# esp32_module.net
KiCad netlist of a schematic drawn in EAGLE
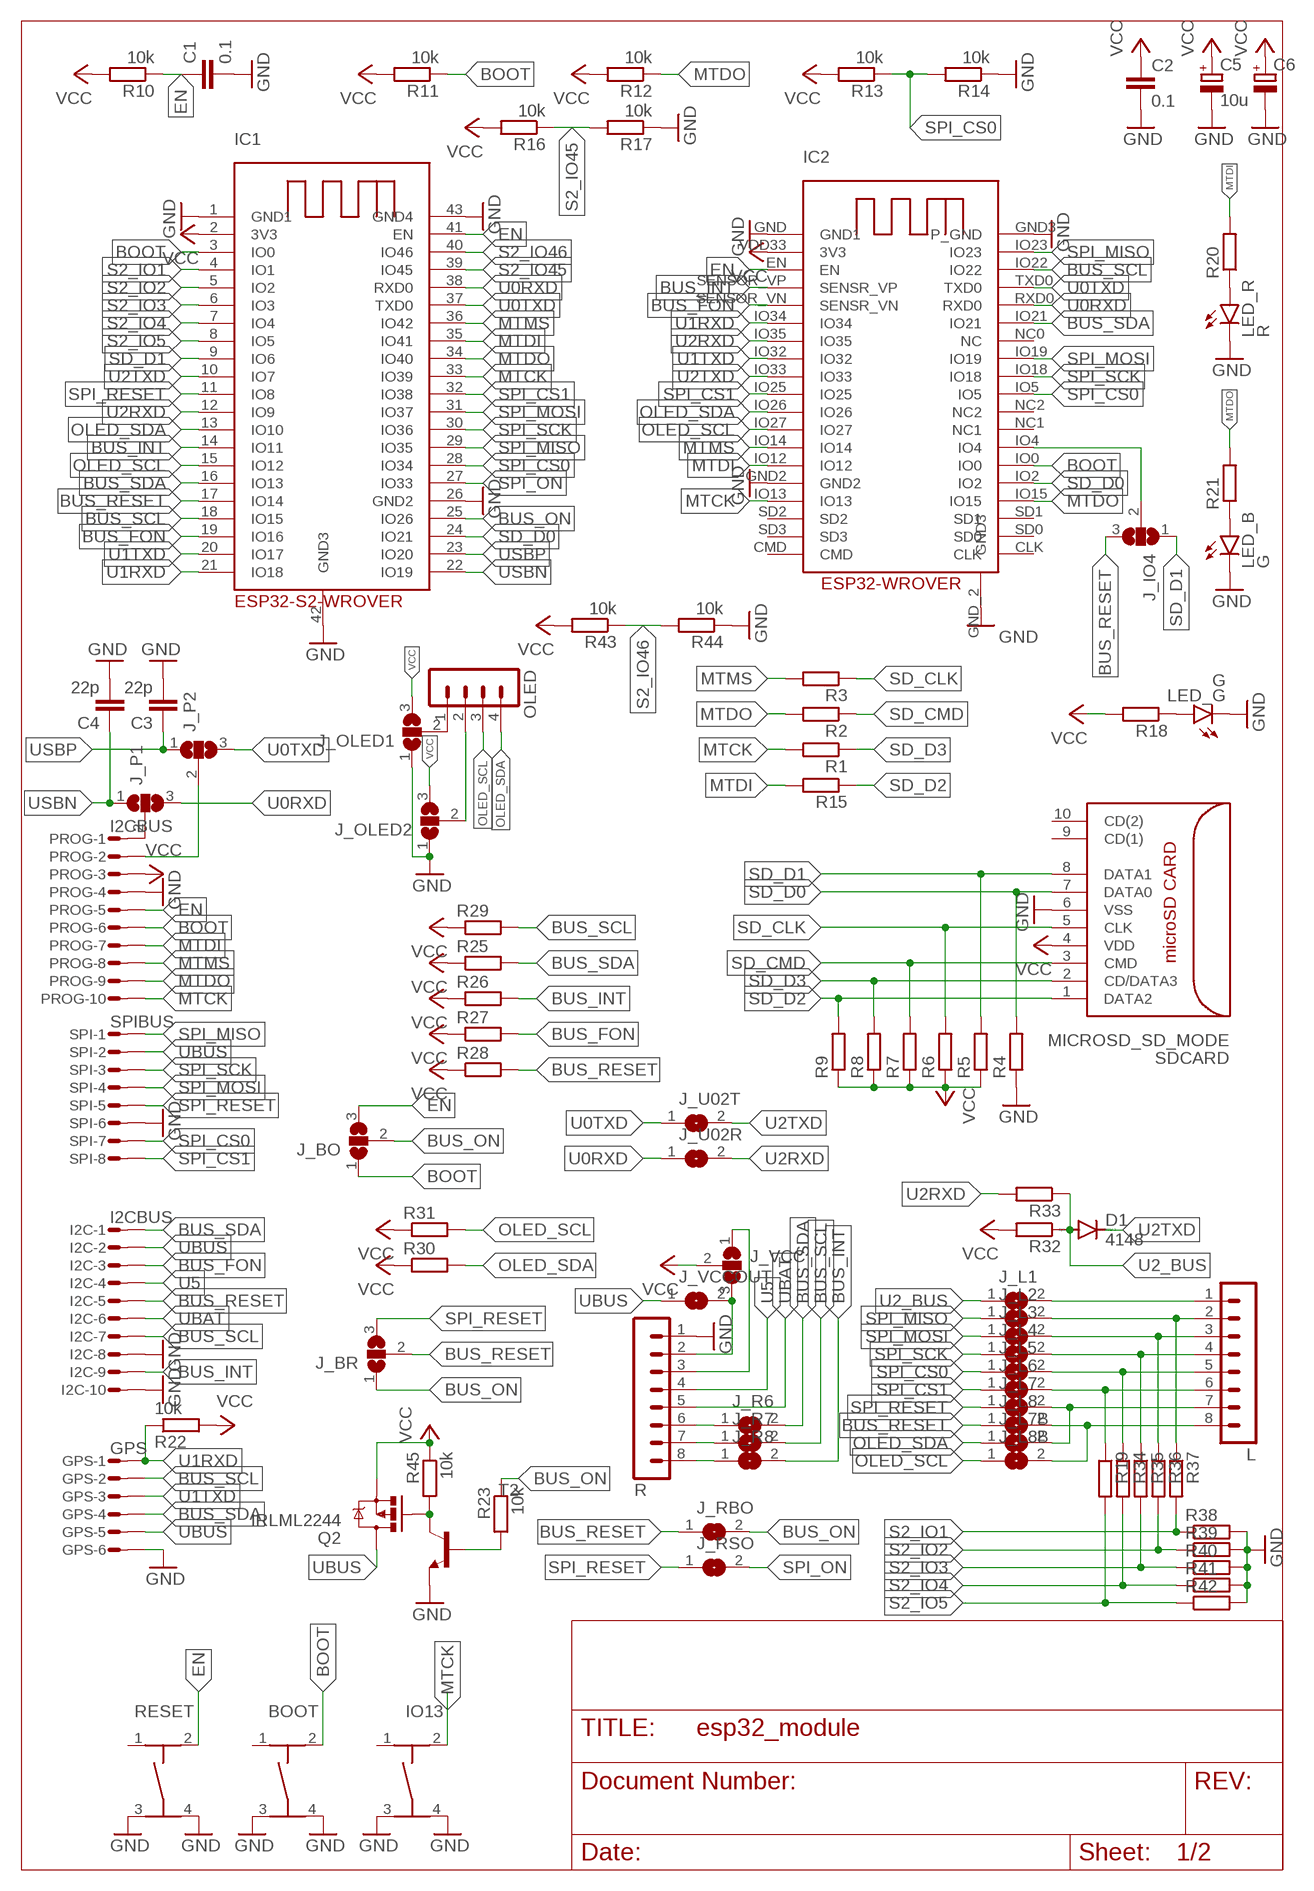
[diagram p0: schematic, sheet 1]

(export (version "E")
  (design (tool "Eeschema 10.0.6"))
  (components
    (comp (ref "BOOT")
      (value "TASTER-9314_SMD")
      (footprint "eagle-import:TASTER-9314_SMD")
      (libsource (lib "eagle-import") (part "TASTER-9314_SMD"))
    )
    (comp (ref "C1")
      (value "0.1")
      (footprint "eagle-import:C0805")
      (libsource (lib "eagle-import") (part "C-EUC0805"))
    )
    (comp (ref "C2")
      (value "0.1")
      (footprint "eagle-import:C0805")
      (libsource (lib "eagle-import") (part "C-EUC0805"))
    )
    (comp (ref "C3")
      (value "22p")
      (footprint "eagle-import:C0805")
      (libsource (lib "eagle-import") (part "C-EUC0805"))
    )
    (comp (ref "C4")
      (value "22p")
      (footprint "eagle-import:C0805")
      (libsource (lib "eagle-import") (part "C-EUC0805"))
    )
    (comp (ref "C5")
      (value "10u")
      (footprint "eagle-import:B_3528-21W")
      (libsource (lib "eagle-import") (part "CPOL-EUB/3528-21W"))
    )
    (comp (ref "C6")
      (value "CPOL-EUC/6032-28R")
      (footprint "eagle-import:C_6032-28R")
      (libsource (lib "eagle-import") (part "CPOL-EUC/6032-28R"))
    )
    (comp (ref "D1")
      (value "4148")
      (footprint "eagle-import:MINIMELF")
      (libsource (lib "eagle-import") (part "DIODE-MINIMELF"))
    )
    (comp (ref "GPS")
      (value "GPS")
      (footprint "eagle-import:MICROMATCH-6SMD")
      (libsource (lib "eagle-import") (part "MICROMATCH-6SMD"))
    )
    (comp (ref "I2C")
      (value "I2CBUS")
      (footprint "eagle-import:MICROMATCH-10SMD")
      (libsource (lib "eagle-import") (part "MICROMATCH-10SMD"))
    )
    (comp (ref "IC1")
      (value "ESP32-S2_WROVER")
      (footprint "eagle-import:ESP32-S2-WROVER")
      (libsource (lib "eagle-import") (part "ESP32-S2_WROVER"))
    )
    (comp (ref "IC2")
      (value "ESP32-WROVER")
      (footprint "eagle-import:ESP32-WROVER")
      (libsource (lib "eagle-import") (part "ESP32-WROVER"))
    )
    (comp (ref "IO13")
      (value "TASTER-9314_SMD")
      (footprint "eagle-import:TASTER-9314_SMD")
      (libsource (lib "eagle-import") (part "TASTER-9314_SMD"))
    )
    (comp (ref "J_BO")
      (value "SJ2W")
      (footprint "eagle-import:SJ_2")
      (libsource (lib "eagle-import") (part "SJ2W"))
    )
    (comp (ref "J_BR")
      (value "SJ2W")
      (footprint "eagle-import:SJ_2")
      (libsource (lib "eagle-import") (part "SJ2W"))
    )
    (comp (ref "J_IO4")
      (value "SJ2W")
      (footprint "eagle-import:SJ_2")
      (libsource (lib "eagle-import") (part "SJ2W"))
    )
    (comp (ref "J_L1")
      (value "SJ")
      (footprint "eagle-import:SJ")
      (libsource (lib "eagle-import") (part "SJ"))
    )
    (comp (ref "J_L2")
      (value "SJ")
      (footprint "eagle-import:SJ")
      (libsource (lib "eagle-import") (part "SJ"))
    )
    (comp (ref "J_L3")
      (value "SJ")
      (footprint "eagle-import:SJ")
      (libsource (lib "eagle-import") (part "SJ"))
    )
    (comp (ref "J_L4")
      (value "SJ")
      (footprint "eagle-import:SJ")
      (libsource (lib "eagle-import") (part "SJ"))
    )
    (comp (ref "J_L5")
      (value "SJ")
      (footprint "eagle-import:SJ")
      (libsource (lib "eagle-import") (part "SJ"))
    )
    (comp (ref "J_L6")
      (value "SJ")
      (footprint "eagle-import:SJ")
      (libsource (lib "eagle-import") (part "SJ"))
    )
    (comp (ref "J_L7")
      (value "SJ")
      (footprint "eagle-import:SJ")
      (libsource (lib "eagle-import") (part "SJ"))
    )
    (comp (ref "J_L7B")
      (value "SJ")
      (footprint "eagle-import:SJ")
      (libsource (lib "eagle-import") (part "SJ"))
    )
    (comp (ref "J_L8")
      (value "SJ")
      (footprint "eagle-import:SJ")
      (libsource (lib "eagle-import") (part "SJ"))
    )
    (comp (ref "J_L8B")
      (value "SJ")
      (footprint "eagle-import:SJ")
      (libsource (lib "eagle-import") (part "SJ"))
    )
    (comp (ref "J_OLED1")
      (value "SJ2W")
      (footprint "eagle-import:SJ_2")
      (libsource (lib "eagle-import") (part "SJ2W"))
    )
    (comp (ref "J_OLED2")
      (value "SJ2W")
      (footprint "eagle-import:SJ_2")
      (libsource (lib "eagle-import") (part "SJ2W"))
    )
    (comp (ref "J_P1")
      (value "SJ2W")
      (footprint "eagle-import:SJ_2")
      (libsource (lib "eagle-import") (part "SJ2W"))
    )
    (comp (ref "J_P2")
      (value "SJ2W")
      (footprint "eagle-import:SJ_2")
      (libsource (lib "eagle-import") (part "SJ2W"))
    )
    (comp (ref "J_R6")
      (value "SJ")
      (footprint "eagle-import:SJ")
      (libsource (lib "eagle-import") (part "SJ"))
    )
    (comp (ref "J_R7")
      (value "SJ")
      (footprint "eagle-import:SJ")
      (libsource (lib "eagle-import") (part "SJ"))
    )
    (comp (ref "J_R8")
      (value "SJ")
      (footprint "eagle-import:SJ")
      (libsource (lib "eagle-import") (part "SJ"))
    )
    (comp (ref "J_RBO")
      (value "SJ")
      (footprint "eagle-import:SJ")
      (libsource (lib "eagle-import") (part "SJ"))
    )
    (comp (ref "J_RSO")
      (value "SJ")
      (footprint "eagle-import:SJ")
      (libsource (lib "eagle-import") (part "SJ"))
    )
    (comp (ref "J_U02R")
      (value "SJ")
      (footprint "eagle-import:SJ")
      (libsource (lib "eagle-import") (part "SJ"))
    )
    (comp (ref "J_U02T")
      (value "SJ")
      (footprint "eagle-import:SJ")
      (libsource (lib "eagle-import") (part "SJ"))
    )
    (comp (ref "J_VCC")
      (value "SJ2W")
      (footprint "eagle-import:SJ_2")
      (libsource (lib "eagle-import") (part "SJ2W"))
    )
    (comp (ref "J_VCCOUT")
      (value "SJ")
      (footprint "eagle-import:SJ")
      (libsource (lib "eagle-import") (part "SJ"))
    )
    (comp (ref "L")
      (value "MA08-1")
      (footprint "eagle-import:MA08-1")
      (libsource (lib "eagle-import") (part "MA08-1"))
    )
    (comp (ref "LED_B")
      (value "G")
      (footprint "eagle-import:CHIPLED_0805")
      (libsource (lib "eagle-import") (part "LEDCHIPLED_0805"))
    )
    (comp (ref "LED_G")
      (value "G")
      (footprint "eagle-import:CHIPLED_0805")
      (libsource (lib "eagle-import") (part "LEDCHIPLED_0805"))
    )
    (comp (ref "LED_R")
      (value "R")
      (footprint "eagle-import:CHIPLED_0805")
      (libsource (lib "eagle-import") (part "LEDCHIPLED_0805"))
    )
    (comp (ref "OLED")
      (value "MA04-1")
      (footprint "eagle-import:MA04-1")
      (libsource (lib "eagle-import") (part "MA04-1"))
    )
    (comp (ref "PROG")
      (value "I2CBUS")
      (footprint "eagle-import:MICROMATCH-10SMD")
      (libsource (lib "eagle-import") (part "MICROMATCH-10SMD"))
    )
    (comp (ref "Q2")
      (value "IRLML2244")
      (footprint "eagle-import:SOT23-3")
      (libsource (lib "eagle-import") (part "MOSFET-PCHANNELIRLML2244"))
    )
    (comp (ref "R")
      (value "MA08-1")
      (footprint "eagle-import:MA08-1")
      (libsource (lib "eagle-import") (part "MA08-1"))
    )
    (comp (ref "R1")
      (value "R-EU_R0805")
      (footprint "eagle-import:R0805")
      (libsource (lib "eagle-import") (part "R-EU_R0805"))
    )
    (comp (ref "R2")
      (value "R-EU_R0805")
      (footprint "eagle-import:R0805")
      (libsource (lib "eagle-import") (part "R-EU_R0805"))
    )
    (comp (ref "R3")
      (value "R-EU_R0805")
      (footprint "eagle-import:R0805")
      (libsource (lib "eagle-import") (part "R-EU_R0805"))
    )
    (comp (ref "R4")
      (value "R-EU_R0805")
      (footprint "eagle-import:R0805")
      (libsource (lib "eagle-import") (part "R-EU_R0805"))
    )
    (comp (ref "R5")
      (value "R-EU_R0805")
      (footprint "eagle-import:R0805")
      (libsource (lib "eagle-import") (part "R-EU_R0805"))
    )
    (comp (ref "R6")
      (value "R-EU_R0805")
      (footprint "eagle-import:R0805")
      (libsource (lib "eagle-import") (part "R-EU_R0805"))
    )
    (comp (ref "R7")
      (value "R-EU_R0805")
      (footprint "eagle-import:R0805")
      (libsource (lib "eagle-import") (part "R-EU_R0805"))
    )
    (comp (ref "R8")
      (value "R-EU_R0805")
      (footprint "eagle-import:R0805")
      (libsource (lib "eagle-import") (part "R-EU_R0805"))
    )
    (comp (ref "R9")
      (value "R-EU_R0805")
      (footprint "eagle-import:R0805")
      (libsource (lib "eagle-import") (part "R-EU_R0805"))
    )
    (comp (ref "R10")
      (value "10k")
      (footprint "eagle-import:R0805")
      (libsource (lib "eagle-import") (part "R-EU_R0805"))
    )
    (comp (ref "R11")
      (value "10k")
      (footprint "eagle-import:R0805")
      (libsource (lib "eagle-import") (part "R-EU_R0805"))
    )
    (comp (ref "R12")
      (value "10k")
      (footprint "eagle-import:R0805")
      (libsource (lib "eagle-import") (part "R-EU_R0805"))
    )
    (comp (ref "R13")
      (value "10k")
      (footprint "eagle-import:R0805")
      (libsource (lib "eagle-import") (part "R-EU_R0805"))
    )
    (comp (ref "R14")
      (value "10k")
      (footprint "eagle-import:R0805")
      (libsource (lib "eagle-import") (part "R-EU_R0805"))
    )
    (comp (ref "R15")
      (value "R-EU_R0805")
      (footprint "eagle-import:R0805")
      (libsource (lib "eagle-import") (part "R-EU_R0805"))
    )
    (comp (ref "R16")
      (value "10k")
      (footprint "eagle-import:R0805")
      (libsource (lib "eagle-import") (part "R-EU_R0805"))
    )
    (comp (ref "R17")
      (value "10k")
      (footprint "eagle-import:R0805")
      (libsource (lib "eagle-import") (part "R-EU_R0805"))
    )
    (comp (ref "R18")
      (value "R-EU_R0603")
      (footprint "eagle-import:R0603")
      (libsource (lib "eagle-import") (part "R-EU_R0603"))
    )
    (comp (ref "R19")
      (value "R-EU_R0805")
      (footprint "eagle-import:R0805")
      (libsource (lib "eagle-import") (part "R-EU_R0805"))
    )
    (comp (ref "R20")
      (value "R-EU_R0603")
      (footprint "eagle-import:R0603")
      (libsource (lib "eagle-import") (part "R-EU_R0603"))
    )
    (comp (ref "R21")
      (value "R-EU_R0603")
      (footprint "eagle-import:R0603")
      (libsource (lib "eagle-import") (part "R-EU_R0603"))
    )
    (comp (ref "R22")
      (value "10k")
      (footprint "eagle-import:R0805")
      (libsource (lib "eagle-import") (part "R-EU_R0805"))
    )
    (comp (ref "R23")
      (value "10k")
      (footprint "eagle-import:R0805")
      (libsource (lib "eagle-import") (part "R-EU_R0805"))
    )
    (comp (ref "R25")
      (value "R-EU_R0805")
      (footprint "eagle-import:R0805")
      (libsource (lib "eagle-import") (part "R-EU_R0805"))
    )
    (comp (ref "R26")
      (value "R-EU_R0805")
      (footprint "eagle-import:R0805")
      (libsource (lib "eagle-import") (part "R-EU_R0805"))
    )
    (comp (ref "R27")
      (value "R-EU_R0805")
      (footprint "eagle-import:R0805")
      (libsource (lib "eagle-import") (part "R-EU_R0805"))
    )
    (comp (ref "R28")
      (value "R-EU_R0805")
      (footprint "eagle-import:R0805")
      (libsource (lib "eagle-import") (part "R-EU_R0805"))
    )
    (comp (ref "R29")
      (value "R-EU_R0805")
      (footprint "eagle-import:R0805")
      (libsource (lib "eagle-import") (part "R-EU_R0805"))
    )
    (comp (ref "R30")
      (value "R-EU_R0805")
      (footprint "eagle-import:R0805")
      (libsource (lib "eagle-import") (part "R-EU_R0805"))
    )
    (comp (ref "R31")
      (value "R-EU_R0805")
      (footprint "eagle-import:R0805")
      (libsource (lib "eagle-import") (part "R-EU_R0805"))
    )
    (comp (ref "R32")
      (value "R-EU_R0805")
      (footprint "eagle-import:R0805")
      (libsource (lib "eagle-import") (part "R-EU_R0805"))
    )
    (comp (ref "R33")
      (value "R-EU_R0805")
      (footprint "eagle-import:R0805")
      (libsource (lib "eagle-import") (part "R-EU_R0805"))
    )
    (comp (ref "R34")
      (value "R-EU_R0805")
      (footprint "eagle-import:R0805")
      (libsource (lib "eagle-import") (part "R-EU_R0805"))
    )
    (comp (ref "R35")
      (value "R-EU_R0805")
      (footprint "eagle-import:R0805")
      (libsource (lib "eagle-import") (part "R-EU_R0805"))
    )
    (comp (ref "R36")
      (value "R-EU_R0805")
      (footprint "eagle-import:R0805")
      (libsource (lib "eagle-import") (part "R-EU_R0805"))
    )
    (comp (ref "R37")
      (value "R-EU_R0805")
      (footprint "eagle-import:R0805")
      (libsource (lib "eagle-import") (part "R-EU_R0805"))
    )
    (comp (ref "R38")
      (value "R-EU_R0805")
      (footprint "eagle-import:R0805")
      (libsource (lib "eagle-import") (part "R-EU_R0805"))
    )
    (comp (ref "R39")
      (value "R-EU_R0805")
      (footprint "eagle-import:R0805")
      (libsource (lib "eagle-import") (part "R-EU_R0805"))
    )
    (comp (ref "R40")
      (value "R-EU_R0805")
      (footprint "eagle-import:R0805")
      (libsource (lib "eagle-import") (part "R-EU_R0805"))
    )
    (comp (ref "R41")
      (value "R-EU_R0805")
      (footprint "eagle-import:R0805")
      (libsource (lib "eagle-import") (part "R-EU_R0805"))
    )
    (comp (ref "R42")
      (value "R-EU_R0805")
      (footprint "eagle-import:R0805")
      (libsource (lib "eagle-import") (part "R-EU_R0805"))
    )
    (comp (ref "R43")
      (value "10k")
      (footprint "eagle-import:R0805")
      (libsource (lib "eagle-import") (part "R-EU_R0805"))
    )
    (comp (ref "R44")
      (value "10k")
      (footprint "eagle-import:R0805")
      (libsource (lib "eagle-import") (part "R-EU_R0805"))
    )
    (comp (ref "R45")
      (value "10k")
      (footprint "eagle-import:R0805")
      (libsource (lib "eagle-import") (part "R-EU_R0805"))
    )
    (comp (ref "RESET")
      (value "TASTER-9314_SMD")
      (footprint "eagle-import:TASTER-9314_SMD")
      (libsource (lib "eagle-import") (part "TASTER-9314_SMD"))
    )
    (comp (ref "SDCARD")
      (value "MICROSD_SD_MODE")
      (footprint "eagle-import:MICRO_SD_CONNECTOR")
      (libsource (lib "eagle-import") (part "MICROSD_SD_MODE"))
    )
    (comp (ref "SPI")
      (value "SPIBUS")
      (footprint "eagle-import:MICROMATCH-8-SMD")
      (libsource (lib "eagle-import") (part "MICROMATCH-8SMD"))
    )
    (comp (ref "T2")
      (value "BC817-16-NPN-SOT23-BEC")
      (footprint "eagle-import:SOT23-BEC")
      (libsource (lib "eagle-import") (part "-NPN-SOT23-BECBC817-16"))
    )
  )
  (nets
    (net (code "1") (name "BOOT") (class "Default")
      (node (ref "BOOT") (pin "2") (pinfunction "2_2") (pintype "passive"))
      (node (ref "IC1") (pin "3") (pinfunction "IO0_3") (pintype "bidirectional"))
      (node (ref "IC2") (pin "IO0") (pinfunction "IO0_IO0") (pintype "bidirectional"))
      (node (ref "J_BO") (pin "1") (pinfunction "1_1") (pintype "passive"))
      (node (ref "PROG") (pin "6") (pinfunction "S_6") (pintype "passive"))
      (node (ref "R11") (pin "1") (pinfunction "1_1") (pintype "passive"))
    )
    (net (code "2") (name "BUS_FON") (class "Default")
      (node (ref "I2C") (pin "3") (pinfunction "S_3") (pintype "passive"))
      (node (ref "IC1") (pin "19") (pinfunction "IO16_19") (pintype "bidirectional"))
      (node (ref "IC2") (pin "SENSOR_VN") (pinfunction "SENSR_VN_SENSOR_VN") (pintype "bidirectional"))
      (node (ref "R27") (pin "2") (pinfunction "2_2") (pintype "passive"))
    )
    (net (code "3") (name "BUS_INT") (class "Default")
      (node (ref "I2C") (pin "9") (pinfunction "S_9") (pintype "passive"))
      (node (ref "IC1") (pin "14") (pinfunction "IO11_14") (pintype "bidirectional"))
      (node (ref "IC2") (pin "SENSOR_VP") (pinfunction "SENSR_VP_SENSOR_VP") (pintype "bidirectional"))
      (node (ref "J_R8") (pin "2") (pinfunction "2_2") (pintype "passive"))
      (node (ref "R26") (pin "2") (pinfunction "2_2") (pintype "passive"))
    )
    (net (code "4") (name "BUS_ON") (class "Default")
      (node (ref "IC1") (pin "25") (pinfunction "IO26_25") (pintype "bidirectional"))
      (node (ref "J_BO") (pin "2") (pinfunction "2_2") (pintype "passive"))
      (node (ref "J_BR") (pin "1") (pinfunction "1_1") (pintype "passive"))
      (node (ref "J_RBO") (pin "2") (pinfunction "2_2") (pintype "passive"))
      (node (ref "R23") (pin "1") (pinfunction "1_1") (pintype "passive"))
    )
    (net (code "5") (name "BUS_RESET") (class "Default")
      (node (ref "I2C") (pin "5") (pinfunction "S_5") (pintype "passive"))
      (node (ref "IC1") (pin "17") (pinfunction "IO14_17") (pintype "bidirectional"))
      (node (ref "J_BR") (pin "2") (pinfunction "2_2") (pintype "passive"))
      (node (ref "J_IO4") (pin "3") (pinfunction "3_3") (pintype "passive"))
      (node (ref "J_L8") (pin "1") (pinfunction "1_1") (pintype "passive"))
      (node (ref "J_RBO") (pin "1") (pinfunction "1_1") (pintype "passive"))
      (node (ref "R28") (pin "2") (pinfunction "2_2") (pintype "passive"))
    )
    (net (code "6") (name "BUS_SCL") (class "Default")
      (node (ref "GPS") (pin "2") (pinfunction "S_2") (pintype "passive"))
      (node (ref "I2C") (pin "7") (pinfunction "S_7") (pintype "passive"))
      (node (ref "IC1") (pin "18") (pinfunction "IO15_18") (pintype "bidirectional"))
      (node (ref "IC2") (pin "IO22") (pinfunction "IO22_IO22") (pintype "bidirectional"))
      (node (ref "J_R7") (pin "2") (pinfunction "2_2") (pintype "passive"))
      (node (ref "R29") (pin "2") (pinfunction "2_2") (pintype "passive"))
    )
    (net (code "7") (name "BUS_SDA") (class "Default")
      (node (ref "GPS") (pin "4") (pinfunction "S_4") (pintype "passive"))
      (node (ref "I2C") (pin "1") (pinfunction "S_1") (pintype "passive"))
      (node (ref "IC1") (pin "16") (pinfunction "IO13_16") (pintype "bidirectional"))
      (node (ref "IC2") (pin "IO21") (pinfunction "IO21_IO21") (pintype "bidirectional"))
      (node (ref "J_R6") (pin "2") (pinfunction "2_2") (pintype "passive"))
      (node (ref "R25") (pin "2") (pinfunction "2_2") (pintype "passive"))
    )
    (net (code "8") (name "EN") (class "Default")
      (node (ref "C1") (pin "1") (pinfunction "1_1") (pintype "passive"))
      (node (ref "IC1") (pin "41") (pinfunction "EN_41") (pintype "input"))
      (node (ref "IC2") (pin "EN") (pinfunction "EN_EN") (pintype "bidirectional"))
      (node (ref "J_BO") (pin "3") (pinfunction "3_3") (pintype "passive"))
      (node (ref "PROG") (pin "5") (pinfunction "S_5") (pintype "passive"))
      (node (ref "R10") (pin "1") (pinfunction "1_1") (pintype "passive"))
      (node (ref "RESET") (pin "2") (pinfunction "2_2") (pintype "passive"))
    )
    (net (code "9") (name "GND") (class "Default")
      (node (ref "BOOT") (pin "3") (pinfunction "3_3") (pintype "passive"))
      (node (ref "BOOT") (pin "4") (pinfunction "4_4") (pintype "passive"))
      (node (ref "C1") (pin "2") (pinfunction "2_2") (pintype "passive"))
      (node (ref "C2") (pin "2") (pinfunction "2_2") (pintype "passive"))
      (node (ref "C3") (pin "2") (pinfunction "2_2") (pintype "passive"))
      (node (ref "C4") (pin "2") (pinfunction "2_2") (pintype "passive"))
      (node (ref "C5") (pin "-") (pinfunction "-_-") (pintype "passive"))
      (node (ref "C6") (pin "-") (pinfunction "-_-") (pintype "passive"))
      (node (ref "GPS") (pin "6") (pinfunction "S_6") (pintype "passive"))
      (node (ref "I2C") (pin "10") (pinfunction "S_10") (pintype "passive"))
      (node (ref "I2C") (pin "8") (pinfunction "S_8") (pintype "passive"))
      (node (ref "IC1") (pin "1") (pinfunction "GND1_1") (pintype "passive"))
      (node (ref "IC1") (pin "26") (pinfunction "GND2_26") (pintype "passive"))
      (node (ref "IC1") (pin "42") (pinfunction "GND3_42") (pintype "passive"))
      (node (ref "IC1") (pin "43") (pinfunction "GND4_43") (pintype "passive"))
      (node (ref "IC2") (pin "GND") (pinfunction "GND1_GND") (pintype "bidirectional"))
      (node (ref "IC2") (pin "GND2") (pinfunction "GND2_GND2") (pintype "bidirectional"))
      (node (ref "IC2") (pin "GND3") (pinfunction "P_GND_GND3") (pintype "bidirectional"))
      (node (ref "IC2") (pin "GND_2") (pinfunction "GND3_GND_2") (pintype "bidirectional"))
      (node (ref "IO13") (pin "3") (pinfunction "3_3") (pintype "passive"))
      (node (ref "IO13") (pin "4") (pinfunction "4_4") (pintype "passive"))
      (node (ref "J_OLED1") (pin "1") (pinfunction "1_1") (pintype "passive"))
      (node (ref "J_OLED2") (pin "1") (pinfunction "1_1") (pintype "passive"))
      (node (ref "LED_B") (pin "C") (pinfunction "C_C") (pintype "passive"))
      (node (ref "LED_G") (pin "C") (pinfunction "C_C") (pintype "passive"))
      (node (ref "LED_R") (pin "C") (pinfunction "C_C") (pintype "passive"))
      (node (ref "PROG") (pin "4") (pinfunction "S_4") (pintype "passive"))
      (node (ref "R") (pin "1") (pinfunction "1_1") (pintype "passive"))
      (node (ref "R14") (pin "1") (pinfunction "1_1") (pintype "passive"))
      (node (ref "R17") (pin "1") (pinfunction "1_1") (pintype "passive"))
      (node (ref "R38") (pin "2") (pinfunction "2_2") (pintype "passive"))
      (node (ref "R39") (pin "2") (pinfunction "2_2") (pintype "passive"))
      (node (ref "R4") (pin "1") (pinfunction "1_1") (pintype "passive"))
      (node (ref "R40") (pin "2") (pinfunction "2_2") (pintype "passive"))
      (node (ref "R41") (pin "2") (pinfunction "2_2") (pintype "passive"))
      (node (ref "R42") (pin "2") (pinfunction "2_2") (pintype "passive"))
      (node (ref "R44") (pin "1") (pinfunction "1_1") (pintype "passive"))
      (node (ref "RESET") (pin "3") (pinfunction "3_3") (pintype "passive"))
      (node (ref "RESET") (pin "4") (pinfunction "4_4") (pintype "passive"))
      (node (ref "SDCARD") (pin "6") (pinfunction "VSS_6") (pintype "bidirectional"))
      (node (ref "SPI") (pin "6") (pinfunction "S_6") (pintype "passive"))
      (node (ref "T2") (pin "E") (pinfunction "E_E") (pintype "passive"))
    )
    (net (code "10") (name "MTCK") (class "Default")
      (node (ref "IC1") (pin "33") (pinfunction "IO39_33") (pintype "bidirectional"))
      (node (ref "IC2") (pin "IO13") (pinfunction "IO13_IO13") (pintype "bidirectional"))
      (node (ref "IO13") (pin "2") (pinfunction "2_2") (pintype "passive"))
      (node (ref "PROG") (pin "10") (pinfunction "S_10") (pintype "passive"))
      (node (ref "R1") (pin "2") (pinfunction "2_2") (pintype "passive"))
    )
    (net (code "11") (name "MTDI") (class "Default")
      (node (ref "IC1") (pin "35") (pinfunction "IO41_35") (pintype "bidirectional"))
      (node (ref "IC2") (pin "IO12") (pinfunction "IO12_IO12") (pintype "bidirectional"))
      (node (ref "PROG") (pin "7") (pinfunction "S_7") (pintype "passive"))
      (node (ref "R15") (pin "2") (pinfunction "2_2") (pintype "passive"))
      (node (ref "R20") (pin "2") (pinfunction "2_2") (pintype "passive"))
    )
    (net (code "12") (name "MTDO") (class "Default")
      (node (ref "IC1") (pin "34") (pinfunction "IO40_34") (pintype "bidirectional"))
      (node (ref "IC2") (pin "IO15") (pinfunction "IO15_IO15") (pintype "bidirectional"))
      (node (ref "PROG") (pin "9") (pinfunction "S_9") (pintype "passive"))
      (node (ref "R12") (pin "1") (pinfunction "1_1") (pintype "passive"))
      (node (ref "R2") (pin "2") (pinfunction "2_2") (pintype "passive"))
      (node (ref "R21") (pin "2") (pinfunction "2_2") (pintype "passive"))
    )
    (net (code "13") (name "MTMS") (class "Default")
      (node (ref "IC1") (pin "36") (pinfunction "IO42_36") (pintype "bidirectional"))
      (node (ref "IC2") (pin "IO14") (pinfunction "IO14_IO14") (pintype "bidirectional"))
      (node (ref "PROG") (pin "8") (pinfunction "S_8") (pintype "passive"))
      (node (ref "R3") (pin "2") (pinfunction "2_2") (pintype "passive"))
    )
    (net (code "14") (name "Net-(IC2-PadIO4)") (class "Default")
      (node (ref "IC2") (pin "IO4") (pinfunction "IO4_IO4") (pintype "bidirectional"))
      (node (ref "J_IO4") (pin "2") (pinfunction "2_2") (pintype "passive"))
    )
    (net (code "15") (name "Net-(J_L1-Pad2)") (class "Default")
      (node (ref "J_L1") (pin "2") (pinfunction "2_2") (pintype "passive"))
      (node (ref "L") (pin "1") (pinfunction "1_1") (pintype "passive"))
    )
    (net (code "16") (name "Net-(J_L2-Pad2)") (class "Default")
      (node (ref "J_L2") (pin "2") (pinfunction "2_2") (pintype "passive"))
      (node (ref "L") (pin "2") (pinfunction "2_2") (pintype "passive"))
      (node (ref "R37") (pin "1") (pinfunction "1_1") (pintype "passive"))
    )
    (net (code "17") (name "Net-(J_L3-Pad2)") (class "Default")
      (node (ref "J_L3") (pin "2") (pinfunction "2_2") (pintype "passive"))
      (node (ref "L") (pin "3") (pinfunction "3_3") (pintype "passive"))
      (node (ref "R36") (pin "1") (pinfunction "1_1") (pintype "passive"))
    )
    (net (code "18") (name "Net-(J_L4-Pad2)") (class "Default")
      (node (ref "J_L4") (pin "2") (pinfunction "2_2") (pintype "passive"))
      (node (ref "L") (pin "4") (pinfunction "4_4") (pintype "passive"))
      (node (ref "R35") (pin "1") (pinfunction "1_1") (pintype "passive"))
    )
    (net (code "19") (name "Net-(J_L5-Pad2)") (class "Default")
      (node (ref "J_L5") (pin "2") (pinfunction "2_2") (pintype "passive"))
      (node (ref "L") (pin "5") (pinfunction "5_5") (pintype "passive"))
      (node (ref "R34") (pin "1") (pinfunction "1_1") (pintype "passive"))
    )
    (net (code "20") (name "Net-(J_L6-Pad2)") (class "Default")
      (node (ref "J_L6") (pin "2") (pinfunction "2_2") (pintype "passive"))
      (node (ref "L") (pin "6") (pinfunction "6_6") (pintype "passive"))
      (node (ref "R19") (pin "1") (pinfunction "1_1") (pintype "passive"))
    )
    (net (code "21") (name "Net-(J_L7-Pad2)") (class "Default")
      (node (ref "J_L7") (pin "2") (pinfunction "2_2") (pintype "passive"))
      (node (ref "J_L7B") (pin "2") (pinfunction "2_2") (pintype "passive"))
      (node (ref "L") (pin "7") (pinfunction "7_7") (pintype "passive"))
    )
    (net (code "22") (name "Net-(J_L8-Pad2)") (class "Default")
      (node (ref "J_L8") (pin "2") (pinfunction "2_2") (pintype "passive"))
      (node (ref "J_L8B") (pin "2") (pinfunction "2_2") (pintype "passive"))
      (node (ref "L") (pin "8") (pinfunction "8_8") (pintype "passive"))
    )
    (net (code "23") (name "Net-(J_OLED1-Pad2)") (class "Default")
      (node (ref "J_OLED1") (pin "2") (pinfunction "2_2") (pintype "passive"))
      (node (ref "OLED") (pin "1") (pinfunction "1_1") (pintype "passive"))
    )
    (net (code "24") (name "Net-(J_OLED2-Pad2)") (class "Default")
      (node (ref "J_OLED2") (pin "2") (pinfunction "2_2") (pintype "passive"))
      (node (ref "OLED") (pin "2") (pinfunction "2_2") (pintype "passive"))
    )
    (net (code "25") (name "Net-(J_R6-Pad1)") (class "Default")
      (node (ref "J_R6") (pin "1") (pinfunction "1_1") (pintype "passive"))
      (node (ref "R") (pin "6") (pinfunction "6_6") (pintype "passive"))
    )
    (net (code "26") (name "Net-(J_R7-Pad1)") (class "Default")
      (node (ref "J_R7") (pin "1") (pinfunction "1_1") (pintype "passive"))
      (node (ref "R") (pin "7") (pinfunction "7_7") (pintype "passive"))
    )
    (net (code "27") (name "Net-(J_R8-Pad1)") (class "Default")
      (node (ref "J_R8") (pin "1") (pinfunction "1_1") (pintype "passive"))
      (node (ref "R") (pin "8") (pinfunction "8_8") (pintype "passive"))
    )
    (net (code "28") (name "Net-(J_VCC-Pad1)") (class "Default")
      (node (ref "J_VCC") (pin "1") (pinfunction "1_1") (pintype "passive"))
      (node (ref "R") (pin "3") (pinfunction "3_3") (pintype "passive"))
    )
    (net (code "29") (name "Net-(J_VCC-Pad3)") (class "Default")
      (node (ref "J_VCC") (pin "3") (pinfunction "3_3") (pintype "passive"))
      (node (ref "J_VCCOUT") (pin "2") (pinfunction "2_2") (pintype "passive"))
      (node (ref "R") (pin "2") (pinfunction "2_2") (pintype "passive"))
    )
    (net (code "30") (name "Net-(LED_B-PadA)") (class "Default")
      (node (ref "LED_B") (pin "A") (pinfunction "A_A") (pintype "passive"))
      (node (ref "R21") (pin "1") (pinfunction "1_1") (pintype "passive"))
    )
    (net (code "31") (name "Net-(LED_G-PadA)") (class "Default")
      (node (ref "LED_G") (pin "A") (pinfunction "A_A") (pintype "passive"))
      (node (ref "R18") (pin "1") (pinfunction "1_1") (pintype "passive"))
    )
    (net (code "32") (name "Net-(LED_R-PadA)") (class "Default")
      (node (ref "LED_R") (pin "A") (pinfunction "A_A") (pintype "passive"))
      (node (ref "R20") (pin "1") (pinfunction "1_1") (pintype "passive"))
    )
    (net (code "33") (name "Net-(PROGA-S)") (class "Default")
      (node (ref "J_P1") (pin "2") (pinfunction "2_2") (pintype "passive"))
      (node (ref "PROG") (pin "1") (pinfunction "S_1") (pintype "passive"))
    )
    (net (code "34") (name "Net-(PROGC-S)") (class "Default")
      (node (ref "J_P2") (pin "2") (pinfunction "2_2") (pintype "passive"))
      (node (ref "PROG") (pin "2") (pinfunction "S_2") (pintype "passive"))
    )
    (net (code "35") (name "Net-(Q2-G)") (class "Default")
      (node (ref "Q2") (pin "1") (pinfunction "G_1") (pintype "passive"))
      (node (ref "R45") (pin "2") (pinfunction "2_2") (pintype "passive"))
      (node (ref "T2") (pin "C") (pinfunction "C_C") (pintype "passive"))
    )
    (net (code "36") (name "Net-(R23-Pad2)") (class "Default")
      (node (ref "R23") (pin "2") (pinfunction "2_2") (pintype "passive"))
      (node (ref "T2") (pin "B") (pinfunction "B_B") (pintype "passive"))
    )
    (net (code "37") (name "OLED_SCL") (class "Default")
      (node (ref "IC1") (pin "15") (pinfunction "IO12_15") (pintype "bidirectional"))
      (node (ref "IC2") (pin "IO27") (pinfunction "IO27_IO27") (pintype "bidirectional"))
      (node (ref "J_L8B") (pin "1") (pinfunction "1_1") (pintype "passive"))
      (node (ref "OLED") (pin "3") (pinfunction "3_3") (pintype "passive"))
      (node (ref "R31") (pin "2") (pinfunction "2_2") (pintype "passive"))
    )
    (net (code "38") (name "OLED_SDA") (class "Default")
      (node (ref "IC1") (pin "13") (pinfunction "IO10_13") (pintype "bidirectional"))
      (node (ref "IC2") (pin "IO26") (pinfunction "IO26_IO26") (pintype "bidirectional"))
      (node (ref "J_L7B") (pin "1") (pinfunction "1_1") (pintype "passive"))
      (node (ref "OLED") (pin "4") (pinfunction "4_4") (pintype "passive"))
      (node (ref "R30") (pin "2") (pinfunction "2_2") (pintype "passive"))
    )
    (net (code "39") (name "S2_IO1") (class "Default")
      (node (ref "IC1") (pin "4") (pinfunction "IO1_4") (pintype "bidirectional"))
      (node (ref "R37") (pin "2") (pinfunction "2_2") (pintype "passive"))
      (node (ref "R38") (pin "1") (pinfunction "1_1") (pintype "passive"))
    )
    (net (code "40") (name "S2_IO2") (class "Default")
      (node (ref "IC1") (pin "5") (pinfunction "IO2_5") (pintype "bidirectional"))
      (node (ref "R36") (pin "2") (pinfunction "2_2") (pintype "passive"))
      (node (ref "R39") (pin "1") (pinfunction "1_1") (pintype "passive"))
    )
    (net (code "41") (name "S2_IO3") (class "Default")
      (node (ref "IC1") (pin "6") (pinfunction "IO3_6") (pintype "bidirectional"))
      (node (ref "R35") (pin "2") (pinfunction "2_2") (pintype "passive"))
      (node (ref "R40") (pin "1") (pinfunction "1_1") (pintype "passive"))
    )
    (net (code "42") (name "S2_IO4") (class "Default")
      (node (ref "IC1") (pin "7") (pinfunction "IO4_7") (pintype "bidirectional"))
      (node (ref "R34") (pin "2") (pinfunction "2_2") (pintype "passive"))
      (node (ref "R41") (pin "1") (pinfunction "1_1") (pintype "passive"))
    )
    (net (code "43") (name "S2_IO5") (class "Default")
      (node (ref "IC1") (pin "8") (pinfunction "IO5_8") (pintype "bidirectional"))
      (node (ref "R19") (pin "2") (pinfunction "2_2") (pintype "passive"))
      (node (ref "R42") (pin "1") (pinfunction "1_1") (pintype "passive"))
    )
    (net (code "44") (name "S2_IO45") (class "Default")
      (node (ref "IC1") (pin "39") (pinfunction "IO45_39") (pintype "bidirectional"))
      (node (ref "R16") (pin "1") (pinfunction "1_1") (pintype "passive"))
      (node (ref "R17") (pin "2") (pinfunction "2_2") (pintype "passive"))
    )
    (net (code "45") (name "S2_IO46") (class "Default")
      (node (ref "IC1") (pin "40") (pinfunction "IO46_40") (pintype "bidirectional"))
      (node (ref "R43") (pin "1") (pinfunction "1_1") (pintype "passive"))
      (node (ref "R44") (pin "2") (pinfunction "2_2") (pintype "passive"))
    )
    (net (code "46") (name "SD_CLK") (class "Default")
      (node (ref "R3") (pin "1") (pinfunction "1_1") (pintype "passive"))
      (node (ref "R6") (pin "2") (pinfunction "2_2") (pintype "passive"))
      (node (ref "SDCARD") (pin "5") (pinfunction "CLK_5") (pintype "bidirectional"))
    )
    (net (code "47") (name "SD_CMD") (class "Default")
      (node (ref "R2") (pin "1") (pinfunction "1_1") (pintype "passive"))
      (node (ref "R7") (pin "2") (pinfunction "2_2") (pintype "passive"))
      (node (ref "SDCARD") (pin "3") (pinfunction "CMD_3") (pintype "bidirectional"))
    )
    (net (code "48") (name "SD_D0") (class "Default")
      (node (ref "IC1") (pin "24") (pinfunction "IO21_24") (pintype "bidirectional"))
      (node (ref "IC2") (pin "IO2") (pinfunction "IO2_IO2") (pintype "bidirectional"))
      (node (ref "R4") (pin "2") (pinfunction "2_2") (pintype "passive"))
      (node (ref "SDCARD") (pin "7") (pinfunction "DATA0_7") (pintype "bidirectional"))
    )
    (net (code "49") (name "SD_D1") (class "Default")
      (node (ref "IC1") (pin "9") (pinfunction "IO6_9") (pintype "bidirectional"))
      (node (ref "J_IO4") (pin "1") (pinfunction "1_1") (pintype "passive"))
      (node (ref "R5") (pin "2") (pinfunction "2_2") (pintype "passive"))
      (node (ref "SDCARD") (pin "8") (pinfunction "DATA1_8") (pintype "bidirectional"))
    )
    (net (code "50") (name "SD_D2") (class "Default")
      (node (ref "R15") (pin "1") (pinfunction "1_1") (pintype "passive"))
      (node (ref "R9") (pin "2") (pinfunction "2_2") (pintype "passive"))
      (node (ref "SDCARD") (pin "1") (pinfunction "DATA2_1") (pintype "bidirectional"))
    )
    (net (code "51") (name "SD_D3") (class "Default")
      (node (ref "R1") (pin "1") (pinfunction "1_1") (pintype "passive"))
      (node (ref "R8") (pin "2") (pinfunction "2_2") (pintype "passive"))
      (node (ref "SDCARD") (pin "2") (pinfunction "CD/DATA3_2") (pintype "bidirectional"))
    )
    (net (code "52") (name "SPI_CS0") (class "Default")
      (node (ref "IC1") (pin "28") (pinfunction "IO34_28") (pintype "bidirectional"))
      (node (ref "IC2") (pin "IO5") (pinfunction "IO5_IO5") (pintype "bidirectional"))
      (node (ref "J_L5") (pin "1") (pinfunction "1_1") (pintype "passive"))
      (node (ref "R13") (pin "1") (pinfunction "1_1") (pintype "passive"))
      (node (ref "R14") (pin "2") (pinfunction "2_2") (pintype "passive"))
      (node (ref "SPI") (pin "7") (pinfunction "S_7") (pintype "passive"))
    )
    (net (code "53") (name "SPI_CS1") (class "Default")
      (node (ref "IC1") (pin "32") (pinfunction "IO38_32") (pintype "bidirectional"))
      (node (ref "IC2") (pin "IO25") (pinfunction "IO25_IO25") (pintype "bidirectional"))
      (node (ref "J_L6") (pin "1") (pinfunction "1_1") (pintype "passive"))
      (node (ref "SPI") (pin "8") (pinfunction "S_8") (pintype "passive"))
    )
    (net (code "54") (name "SPI_MISO") (class "Default")
      (node (ref "IC1") (pin "29") (pinfunction "IO35_29") (pintype "bidirectional"))
      (node (ref "IC2") (pin "IO23") (pinfunction "IO23_IO23") (pintype "bidirectional"))
      (node (ref "J_L2") (pin "1") (pinfunction "1_1") (pintype "passive"))
      (node (ref "SPI") (pin "1") (pinfunction "S_1") (pintype "passive"))
    )
    (net (code "55") (name "SPI_MOSI") (class "Default")
      (node (ref "IC1") (pin "31") (pinfunction "IO37_31") (pintype "bidirectional"))
      (node (ref "IC2") (pin "IO19") (pinfunction "IO19_IO19") (pintype "bidirectional"))
      (node (ref "J_L3") (pin "1") (pinfunction "1_1") (pintype "passive"))
      (node (ref "SPI") (pin "4") (pinfunction "S_4") (pintype "passive"))
    )
    (net (code "56") (name "SPI_ON") (class "Default")
      (node (ref "IC1") (pin "27") (pinfunction "IO33_27") (pintype "bidirectional"))
      (node (ref "J_RSO") (pin "2") (pinfunction "2_2") (pintype "passive"))
    )
    (net (code "57") (name "SPI_RESET") (class "Default")
      (node (ref "IC1") (pin "11") (pinfunction "IO8_11") (pintype "bidirectional"))
      (node (ref "J_BR") (pin "3") (pinfunction "3_3") (pintype "passive"))
      (node (ref "J_L7") (pin "1") (pinfunction "1_1") (pintype "passive"))
      (node (ref "J_RSO") (pin "1") (pinfunction "1_1") (pintype "passive"))
      (node (ref "SPI") (pin "5") (pinfunction "S_5") (pintype "passive"))
    )
    (net (code "58") (name "SPI_SCK") (class "Default")
      (node (ref "IC1") (pin "30") (pinfunction "IO36_30") (pintype "bidirectional"))
      (node (ref "IC2") (pin "IO18") (pinfunction "IO18_IO18") (pintype "bidirectional"))
      (node (ref "J_L4") (pin "1") (pinfunction "1_1") (pintype "passive"))
      (node (ref "SPI") (pin "3") (pinfunction "S_3") (pintype "passive"))
    )
    (net (code "59") (name "U0RXD") (class "Default")
      (node (ref "IC1") (pin "38") (pinfunction "RXD0_38") (pintype "input"))
      (node (ref "IC2") (pin "RXD0") (pinfunction "RXD0_RXD0") (pintype "bidirectional"))
      (node (ref "J_P1") (pin "3") (pinfunction "3_3") (pintype "passive"))
      (node (ref "J_U02R") (pin "1") (pinfunction "1_1") (pintype "passive"))
    )
    (net (code "60") (name "U0TXD") (class "Default")
      (node (ref "IC1") (pin "37") (pinfunction "TXD0_37") (pintype "output"))
      (node (ref "IC2") (pin "TXD0") (pinfunction "TXD0_TXD0") (pintype "bidirectional"))
      (node (ref "J_P2") (pin "3") (pinfunction "3_3") (pintype "passive"))
      (node (ref "J_U02T") (pin "1") (pinfunction "1_1") (pintype "passive"))
    )
    (net (code "61") (name "U1RXD") (class "Default")
      (node (ref "GPS") (pin "1") (pinfunction "S_1") (pintype "passive"))
      (node (ref "IC1") (pin "21") (pinfunction "IO18_21") (pintype "bidirectional"))
      (node (ref "IC2") (pin "IO34") (pinfunction "IO34_IO34") (pintype "bidirectional"))
      (node (ref "R22") (pin "1") (pinfunction "1_1") (pintype "passive"))
    )
    (net (code "62") (name "U1TXD") (class "Default")
      (node (ref "GPS") (pin "3") (pinfunction "S_3") (pintype "passive"))
      (node (ref "IC1") (pin "20") (pinfunction "IO17_20") (pintype "bidirectional"))
      (node (ref "IC2") (pin "IO32") (pinfunction "IO32_IO32") (pintype "bidirectional"))
    )
    (net (code "63") (name "U2RXD") (class "Default")
      (node (ref "IC1") (pin "12") (pinfunction "IO9_12") (pintype "bidirectional"))
      (node (ref "IC2") (pin "IO35") (pinfunction "IO35_IO35") (pintype "bidirectional"))
      (node (ref "J_U02R") (pin "2") (pinfunction "2_2") (pintype "passive"))
      (node (ref "R33") (pin "2") (pinfunction "2_2") (pintype "passive"))
    )
    (net (code "64") (name "U2TXD") (class "Default")
      (node (ref "D1") (pin "C") (pinfunction "C_C") (pintype "passive"))
      (node (ref "IC1") (pin "10") (pinfunction "IO7_10") (pintype "bidirectional"))
      (node (ref "IC2") (pin "IO33") (pinfunction "IO33_IO33") (pintype "bidirectional"))
      (node (ref "J_U02T") (pin "2") (pinfunction "2_2") (pintype "passive"))
    )
    (net (code "65") (name "U2_BUS") (class "Default")
      (node (ref "D1") (pin "A") (pinfunction "A_A") (pintype "passive"))
      (node (ref "J_L1") (pin "1") (pinfunction "1_1") (pintype "passive"))
      (node (ref "R32") (pin "1") (pinfunction "1_1") (pintype "passive"))
      (node (ref "R33") (pin "1") (pinfunction "1_1") (pintype "passive"))
    )
    (net (code "66") (name "U5") (class "Default")
      (node (ref "I2C") (pin "4") (pinfunction "S_4") (pintype "passive"))
      (node (ref "R") (pin "4") (pinfunction "4_4") (pintype "passive"))
    )
    (net (code "67") (name "UBAT") (class "Default")
      (node (ref "I2C") (pin "6") (pinfunction "S_6") (pintype "passive"))
      (node (ref "R") (pin "5") (pinfunction "5_5") (pintype "passive"))
    )
    (net (code "68") (name "UBUS") (class "Default")
      (node (ref "GPS") (pin "5") (pinfunction "S_5") (pintype "passive"))
      (node (ref "I2C") (pin "2") (pinfunction "S_2") (pintype "passive"))
      (node (ref "J_VCCOUT") (pin "1") (pinfunction "1_1") (pintype "passive"))
      (node (ref "Q2") (pin "3") (pinfunction "D_3") (pintype "passive"))
      (node (ref "SPI") (pin "2") (pinfunction "S_2") (pintype "passive"))
    )
    (net (code "69") (name "USBN") (class "Default")
      (node (ref "C4") (pin "1") (pinfunction "1_1") (pintype "passive"))
      (node (ref "IC1") (pin "22") (pinfunction "IO19_22") (pintype "bidirectional"))
      (node (ref "J_P1") (pin "1") (pinfunction "1_1") (pintype "passive"))
    )
    (net (code "70") (name "USBP") (class "Default")
      (node (ref "C3") (pin "1") (pinfunction "1_1") (pintype "passive"))
      (node (ref "IC1") (pin "23") (pinfunction "IO20_23") (pintype "bidirectional"))
      (node (ref "J_P2") (pin "1") (pinfunction "1_1") (pintype "passive"))
    )
    (net (code "71") (name "VCC") (class "Default")
      (node (ref "C2") (pin "1") (pinfunction "1_1") (pintype "passive"))
      (node (ref "C5") (pin "+") (pinfunction "+_+") (pintype "passive"))
      (node (ref "C6") (pin "+") (pinfunction "+_+") (pintype "passive"))
      (node (ref "IC1") (pin "2") (pinfunction "3V3_2") (pintype "bidirectional"))
      (node (ref "IC2") (pin "VDD33") (pinfunction "3V3_VDD33") (pintype "bidirectional"))
      (node (ref "J_OLED1") (pin "3") (pinfunction "3_3") (pintype "passive"))
      (node (ref "J_OLED2") (pin "3") (pinfunction "3_3") (pintype "passive"))
      (node (ref "J_VCC") (pin "2") (pinfunction "2_2") (pintype "passive"))
      (node (ref "PROG") (pin "3") (pinfunction "S_3") (pintype "passive"))
      (node (ref "Q2") (pin "2") (pinfunction "S_2") (pintype "passive"))
      (node (ref "R10") (pin "2") (pinfunction "2_2") (pintype "passive"))
      (node (ref "R11") (pin "2") (pinfunction "2_2") (pintype "passive"))
      (node (ref "R12") (pin "2") (pinfunction "2_2") (pintype "passive"))
      (node (ref "R13") (pin "2") (pinfunction "2_2") (pintype "passive"))
      (node (ref "R16") (pin "2") (pinfunction "2_2") (pintype "passive"))
      (node (ref "R18") (pin "2") (pinfunction "2_2") (pintype "passive"))
      (node (ref "R22") (pin "2") (pinfunction "2_2") (pintype "passive"))
      (node (ref "R25") (pin "1") (pinfunction "1_1") (pintype "passive"))
      (node (ref "R26") (pin "1") (pinfunction "1_1") (pintype "passive"))
      (node (ref "R27") (pin "1") (pinfunction "1_1") (pintype "passive"))
      (node (ref "R28") (pin "1") (pinfunction "1_1") (pintype "passive"))
      (node (ref "R29") (pin "1") (pinfunction "1_1") (pintype "passive"))
      (node (ref "R30") (pin "1") (pinfunction "1_1") (pintype "passive"))
      (node (ref "R31") (pin "1") (pinfunction "1_1") (pintype "passive"))
      (node (ref "R32") (pin "2") (pinfunction "2_2") (pintype "passive"))
      (node (ref "R43") (pin "2") (pinfunction "2_2") (pintype "passive"))
      (node (ref "R45") (pin "1") (pinfunction "1_1") (pintype "passive"))
      (node (ref "R5") (pin "1") (pinfunction "1_1") (pintype "passive"))
      (node (ref "R6") (pin "1") (pinfunction "1_1") (pintype "passive"))
      (node (ref "R7") (pin "1") (pinfunction "1_1") (pintype "passive"))
      (node (ref "R8") (pin "1") (pinfunction "1_1") (pintype "passive"))
      (node (ref "R9") (pin "1") (pinfunction "1_1") (pintype "passive"))
      (node (ref "SDCARD") (pin "4") (pinfunction "VDD_4") (pintype "bidirectional"))
    )
    (net (code "72") (name "unconnected-(BOOT-Pad1)") (class "Default")
      (node (ref "BOOT") (pin "1") (pinfunction "1_1") (pintype "passive"))
    )
    (net (code "73") (name "unconnected-(IC2-NC-PadNC0)") (class "Default")
      (node (ref "IC2") (pin "NC0") (pinfunction "NC_NC0") (pintype "bidirectional"))
    )
    (net (code "74") (name "unconnected-(IC2-PadCLK)") (class "Default")
      (node (ref "IC2") (pin "CLK") (pinfunction "CLK_CLK") (pintype "bidirectional"))
    )
    (net (code "75") (name "unconnected-(IC2-PadCMD)") (class "Default")
      (node (ref "IC2") (pin "CMD") (pinfunction "CMD_CMD") (pintype "bidirectional"))
    )
    (net (code "76") (name "unconnected-(IC2-PadNC1)") (class "Default")
      (node (ref "IC2") (pin "NC1") (pinfunction "NC1_NC1") (pintype "bidirectional"))
    )
    (net (code "77") (name "unconnected-(IC2-PadNC2)") (class "Default")
      (node (ref "IC2") (pin "NC2") (pinfunction "NC2_NC2") (pintype "bidirectional"))
    )
    (net (code "78") (name "unconnected-(IC2-PadSD0)") (class "Default")
      (node (ref "IC2") (pin "SD0") (pinfunction "SD0_SD0") (pintype "bidirectional"))
    )
    (net (code "79") (name "unconnected-(IC2-PadSD1)") (class "Default")
      (node (ref "IC2") (pin "SD1") (pinfunction "SD1_SD1") (pintype "bidirectional"))
    )
    (net (code "80") (name "unconnected-(IC2-PadSD2)") (class "Default")
      (node (ref "IC2") (pin "SD2") (pinfunction "SD2_SD2") (pintype "bidirectional"))
    )
    (net (code "81") (name "unconnected-(IC2-PadSD3)") (class "Default")
      (node (ref "IC2") (pin "SD3") (pinfunction "SD3_SD3") (pintype "bidirectional"))
    )
    (net (code "82") (name "unconnected-(IO13-Pad1)") (class "Default")
      (node (ref "IO13") (pin "1") (pinfunction "1_1") (pintype "passive"))
    )
    (net (code "83") (name "unconnected-(RESET-Pad1)") (class "Default")
      (node (ref "RESET") (pin "1") (pinfunction "1_1") (pintype "passive"))
    )
    (net (code "84") (name "unconnected-(SDCARD-CD(1)-Pad9)") (class "Default")
      (node (ref "SDCARD") (pin "9") (pinfunction "CD(1)_9") (pintype "bidirectional"))
    )
    (net (code "85") (name "unconnected-(SDCARD-CD(2)-Pad10)") (class "Default")
      (node (ref "SDCARD") (pin "10") (pinfunction "CD(2)_10") (pintype "bidirectional"))
    )
  )
)
